# FPGAIO.net
KiCad netlist of a schematic drawn in Altium Designer
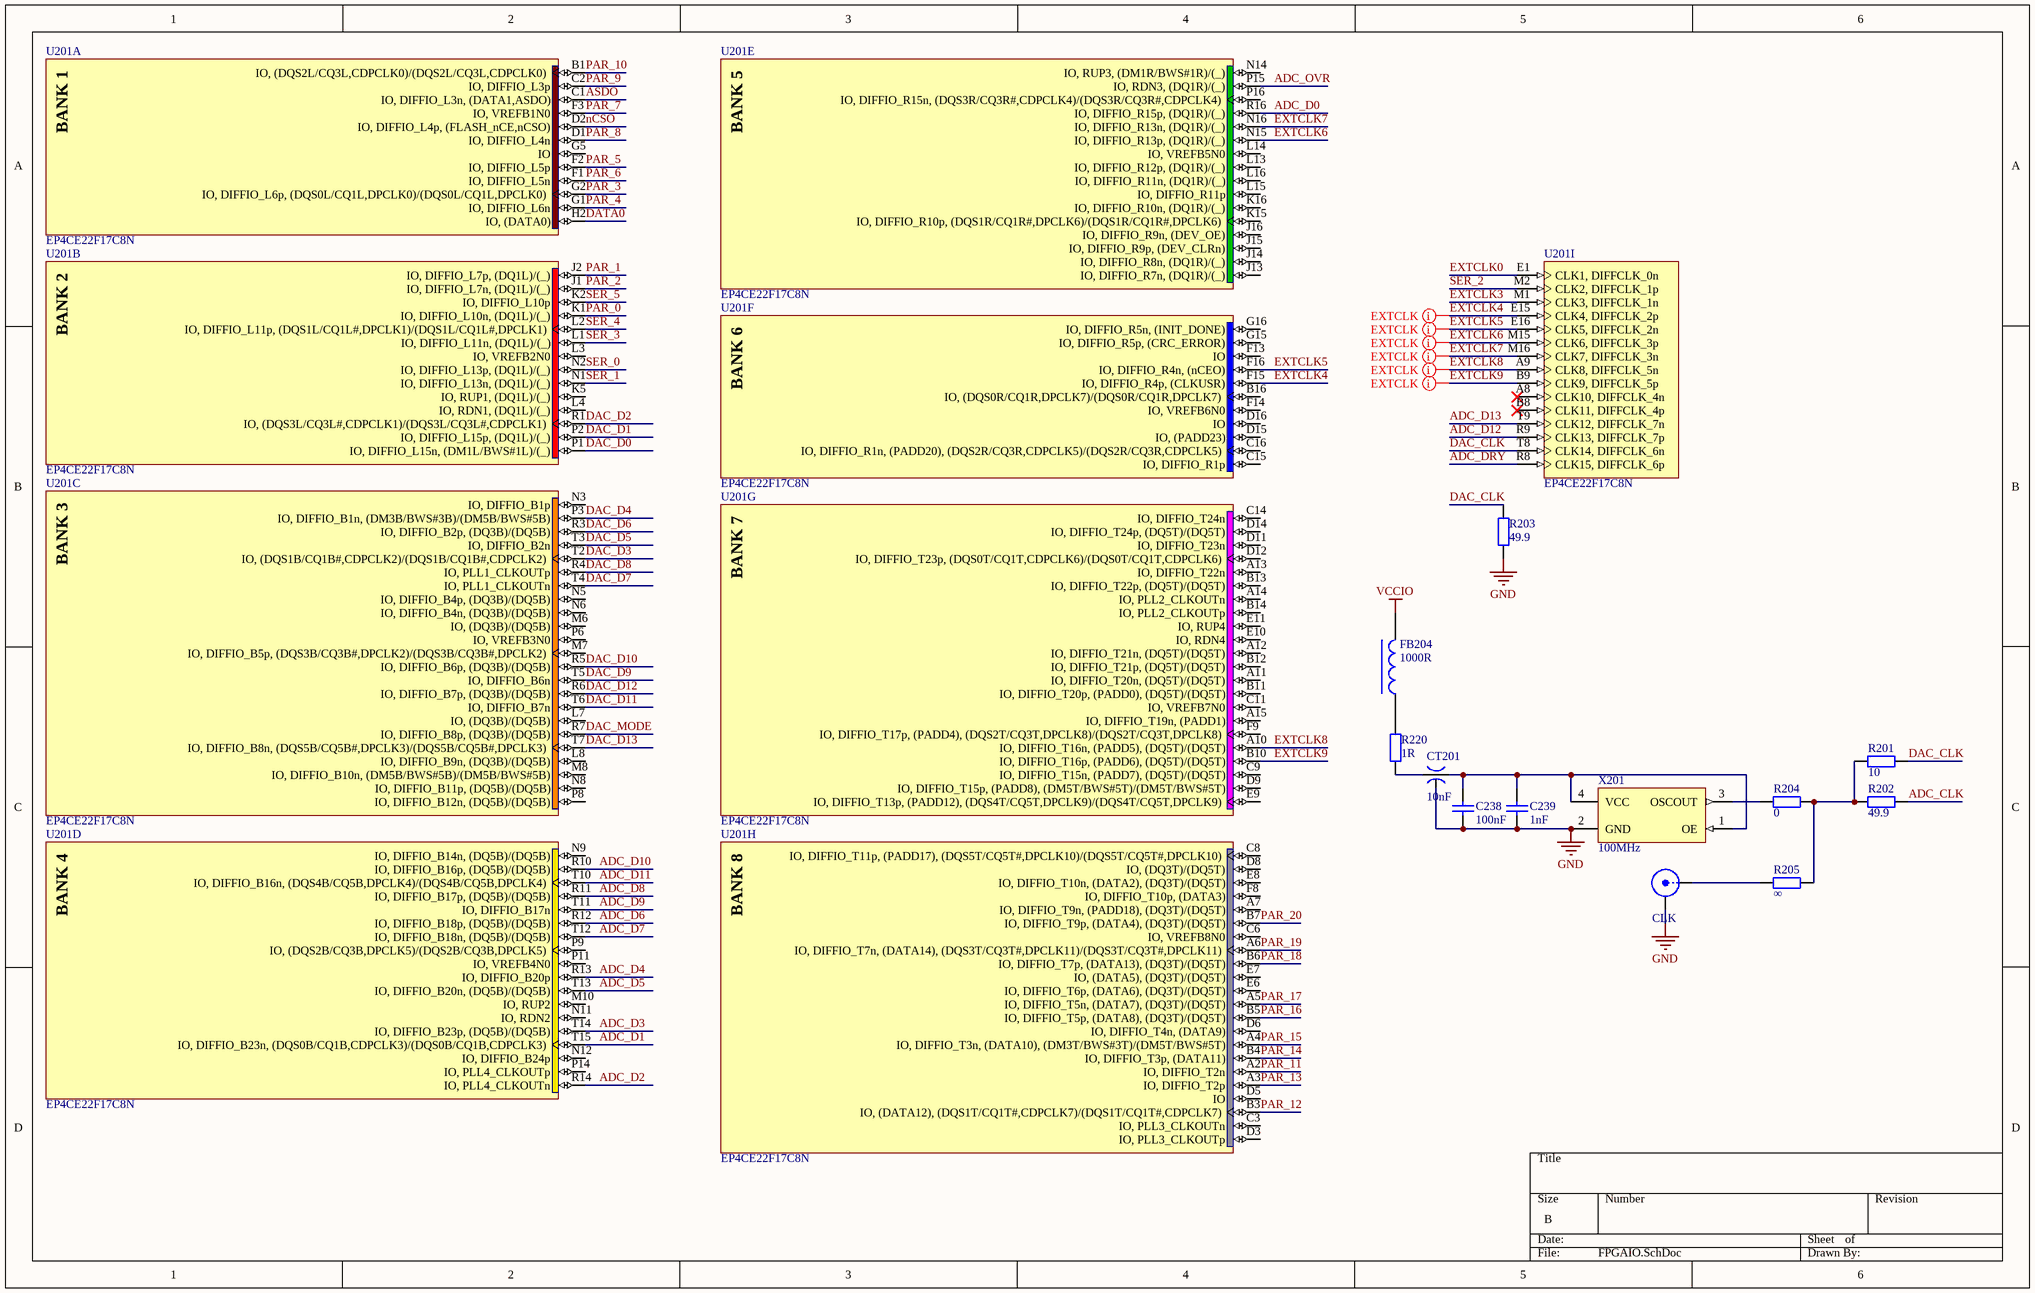
[diagram p0: FPGAIO.SchDoc]

(export (version "E")
  (design (tool "Eeschema 10.0.6"))
  (components
    (comp (ref "C238")
      (value "100nF")
      (footprint "0402C")
      (description "MLCC")
      (libsource (lib "Misc") (part "MLCC"))
    )
    (comp (ref "C239")
      (value "1nF")
      (footprint "0402C")
      (description "MLCC")
      (libsource (lib "Misc") (part "MLCC"))
    )
    (comp (ref "CLK")
      (value "SMA")
      (footprint "SMA-V-NARROW")
      (description "SMA Connector")
      (libsource (lib "SMA") (part "SMA"))
    )
    (comp (ref "CT201")
      (value "10nF")
      (footprint "CAPC0603TH")
      (description "3-terminal capacitor")
      (fields (field (name "Comment") "CAP-TH"))
      (libsource (lib "Misc") (part "CAP-TH"))
    )
    (comp (ref "FB204")
      (value "1000R")
      (footprint "0603L")
      (description "FerriteBead")
      (libsource (lib "Misc") (part "FerriteBead"))
    )
    (comp (ref "R201")
      (value "10")
      (footprint "0402R")
      (description "Resistor")
      (libsource (lib "") (part "Resistor_1"))
    )
    (comp (ref "R202")
      (value "49.9")
      (footprint "0402R")
      (description "Resistor")
      (libsource (lib "") (part "Resistor_1"))
    )
    (comp (ref "R203")
      (value "49.9")
      (footprint "0402R")
      (description "Resistor")
      (libsource (lib "Misc") (part "Resistor"))
    )
    (comp (ref "R204")
      (value "0")
      (footprint "0402R")
      (description "Resistor")
      (libsource (lib "") (part "Resistor_1"))
    )
    (comp (ref "R205")
      (value "∞")
      (footprint "0402R")
      (description "Resistor")
      (libsource (lib "") (part "Resistor_1"))
    )
    (comp (ref "R220")
      (value "1R")
      (footprint "0603R")
      (description "Resistor")
      (libsource (lib "Misc") (part "Resistor"))
    )
    (comp (ref "U201")
      (value "EP4CE22F17C8N")
      (footprint "FBGA256_A-155")
      (fields (field (name "MANUFACTURER") "Altera"))
      (libsource (lib "Altera Cyclone IV E") (part "EP4CE22F17C8N"))
    )
    (comp (ref "X201")
      (value "100MHz")
      (footprint "XTAL-7050")
      (description "Oscillator")
      (libsource (lib "XTAL") (part "Oscillator"))
    )
  )
  (nets
    (net (code "1") (name "/ADC_CLK") (class "Default")
      (node (ref "R202") (pin "2") (pinfunction "2_2") (pintype "passive"))
    )
    (net (code "2") (name "/ADC_D0") (class "Default")
      (node (ref "U201") (pin "R16") (pinfunction "IO,_DIFFIO_R15p,_(DQ1R)/(_)_R16") (pintype "bidirectional"))
    )
    (net (code "3") (name "/ADC_D1") (class "Default")
      (node (ref "U201") (pin "T15") (pinfunction "IO,_DIFFIO_B23n,_(DQS0B/CQ1B,CDPCLK3)/(DQS0B/CQ1B,CDPCLK3)_T15") (pintype "bidirectional"))
    )
    (net (code "4") (name "/ADC_D2") (class "Default")
      (node (ref "U201") (pin "R14") (pinfunction "IO,_PLL4_CLKOUTn_R14") (pintype "bidirectional"))
    )
    (net (code "5") (name "/ADC_D3") (class "Default")
      (node (ref "U201") (pin "T14") (pinfunction "IO,_DIFFIO_B23p,_(DQ5B)/(DQ5B)_T14") (pintype "bidirectional"))
    )
    (net (code "6") (name "/ADC_D4") (class "Default")
      (node (ref "U201") (pin "R13") (pinfunction "IO,_DIFFIO_B20p_R13") (pintype "bidirectional"))
    )
    (net (code "7") (name "/ADC_D5") (class "Default")
      (node (ref "U201") (pin "T13") (pinfunction "IO,_DIFFIO_B20n,_(DQ5B)/(DQ5B)_T13") (pintype "bidirectional"))
    )
    (net (code "8") (name "/ADC_D6") (class "Default")
      (node (ref "U201") (pin "R12") (pinfunction "IO,_DIFFIO_B18p,_(DQ5B)/(DQ5B)_R12") (pintype "bidirectional"))
    )
    (net (code "9") (name "/ADC_D7") (class "Default")
      (node (ref "U201") (pin "T12") (pinfunction "IO,_DIFFIO_B18n,_(DQ5B)/(DQ5B)_T12") (pintype "bidirectional"))
    )
    (net (code "10") (name "/ADC_D8") (class "Default")
      (node (ref "U201") (pin "R11") (pinfunction "IO,_DIFFIO_B17p,_(DQ5B)/(DQ5B)_R11") (pintype "bidirectional"))
    )
    (net (code "11") (name "/ADC_D9") (class "Default")
      (node (ref "U201") (pin "T11") (pinfunction "IO,_DIFFIO_B17n_T11") (pintype "bidirectional"))
    )
    (net (code "12") (name "/ADC_D10") (class "Default")
      (node (ref "U201") (pin "R10") (pinfunction "IO,_DIFFIO_B16p,_(DQ5B)/(DQ5B)_R10") (pintype "bidirectional"))
    )
    (net (code "13") (name "/ADC_D11") (class "Default")
      (node (ref "U201") (pin "T10") (pinfunction "IO,_DIFFIO_B16n,_(DQS4B/CQ5B,DPCLK4)/(DQS4B/CQ5B,DPCLK4)_T10") (pintype "bidirectional"))
    )
    (net (code "14") (name "/ADC_D12") (class "Default")
      (node (ref "U201") (pin "R9") (pinfunction "CLK13,_DIFFCLK_7p_R9") (pintype "input"))
    )
    (net (code "15") (name "/ADC_D13") (class "Default")
      (node (ref "U201") (pin "T9") (pinfunction "CLK12,_DIFFCLK_7n_T9") (pintype "input"))
    )
    (net (code "16") (name "/ADC_DRY") (class "Default")
      (node (ref "U201") (pin "R8") (pinfunction "CLK15,_DIFFCLK_6p_R8") (pintype "input"))
    )
    (net (code "17") (name "/ADC_OVR") (class "Default")
      (node (ref "U201") (pin "P15") (pinfunction "IO,_RDN3,_(DQ1R)/(_)_P15") (pintype "bidirectional"))
    )
    (net (code "18") (name "/ASDO") (class "Default")
      (node (ref "U201") (pin "C1") (pinfunction "IO,_DIFFIO_L3n,_(DATA1,ASDO)_C1") (pintype "bidirectional"))
    )
    (net (code "19") (name "/DAC_CLK") (class "Default")
      (node (ref "R201") (pin "2") (pinfunction "2_2") (pintype "passive"))
      (node (ref "R203") (pin "2") (pinfunction "2_2") (pintype "passive"))
      (node (ref "U201") (pin "T8") (pinfunction "CLK14,_DIFFCLK_6n_T8") (pintype "input"))
    )
    (net (code "20") (name "/DAC_D0") (class "Default")
      (node (ref "U201") (pin "P1") (pinfunction "IO,_DIFFIO_L15n,_(DM1L/BWS#1L)/(_)_P1") (pintype "bidirectional"))
    )
    (net (code "21") (name "/DAC_D1") (class "Default")
      (node (ref "U201") (pin "P2") (pinfunction "IO,_DIFFIO_L15p,_(DQ1L)/(_)_P2") (pintype "bidirectional"))
    )
    (net (code "22") (name "/DAC_D2") (class "Default")
      (node (ref "U201") (pin "R1") (pinfunction "IO,_(DQS3L/CQ3L#,CDPCLK1)/(DQS3L/CQ3L#,CDPCLK1)_R1") (pintype "bidirectional"))
    )
    (net (code "23") (name "/DAC_D3") (class "Default")
      (node (ref "U201") (pin "T2") (pinfunction "IO,_(DQS1B/CQ1B#,CDPCLK2)/(DQS1B/CQ1B#,CDPCLK2)_T2") (pintype "bidirectional"))
    )
    (net (code "24") (name "/DAC_D4") (class "Default")
      (node (ref "U201") (pin "P3") (pinfunction "IO,_DIFFIO_B1n,_(DM3B/BWS#3B)/(DM5B/BWS#5B)_P3") (pintype "bidirectional"))
    )
    (net (code "25") (name "/DAC_D5") (class "Default")
      (node (ref "U201") (pin "T3") (pinfunction "IO,_DIFFIO_B2n_T3") (pintype "bidirectional"))
    )
    (net (code "26") (name "/DAC_D6") (class "Default")
      (node (ref "U201") (pin "R3") (pinfunction "IO,_DIFFIO_B2p,_(DQ3B)/(DQ5B)_R3") (pintype "bidirectional"))
    )
    (net (code "27") (name "/DAC_D7") (class "Default")
      (node (ref "U201") (pin "T4") (pinfunction "IO,_PLL1_CLKOUTn_T4") (pintype "bidirectional"))
    )
    (net (code "28") (name "/DAC_D8") (class "Default")
      (node (ref "U201") (pin "R4") (pinfunction "IO,_PLL1_CLKOUTp_R4") (pintype "bidirectional"))
    )
    (net (code "29") (name "/DAC_D9") (class "Default")
      (node (ref "U201") (pin "T5") (pinfunction "IO,_DIFFIO_B6n_T5") (pintype "bidirectional"))
    )
    (net (code "30") (name "/DAC_D10") (class "Default")
      (node (ref "U201") (pin "R5") (pinfunction "IO,_DIFFIO_B6p,_(DQ3B)/(DQ5B)_R5") (pintype "bidirectional"))
    )
    (net (code "31") (name "/DAC_D11") (class "Default")
      (node (ref "U201") (pin "T6") (pinfunction "IO,_DIFFIO_B7n_T6") (pintype "bidirectional"))
    )
    (net (code "32") (name "/DAC_D12") (class "Default")
      (node (ref "U201") (pin "R6") (pinfunction "IO,_DIFFIO_B7p,_(DQ3B)/(DQ5B)_R6") (pintype "bidirectional"))
    )
    (net (code "33") (name "/DAC_D13") (class "Default")
      (node (ref "U201") (pin "T7") (pinfunction "IO,_DIFFIO_B8n,_(DQS5B/CQ5B#,DPCLK3)/(DQS5B/CQ5B#,DPCLK3)_T7") (pintype "bidirectional"))
    )
    (net (code "34") (name "/DAC_MODE") (class "Default")
      (node (ref "U201") (pin "R7") (pinfunction "IO,_DIFFIO_B8p,_(DQ3B)/(DQ5B)_R7") (pintype "bidirectional"))
    )
    (net (code "35") (name "/DATA0") (class "Default")
      (node (ref "U201") (pin "H2") (pinfunction "IO,_(DATA0)_H2") (pintype "bidirectional"))
    )
    (net (code "36") (name "/EXTCLK0") (class "Default")
      (node (ref "U201") (pin "E1") (pinfunction "CLK1,_DIFFCLK_0n_E1") (pintype "input"))
    )
    (net (code "37") (name "/EXTCLK3") (class "Default")
      (node (ref "U201") (pin "M1") (pinfunction "CLK3,_DIFFCLK_1n_M1") (pintype "input"))
    )
    (net (code "38") (name "/EXTCLK4") (class "Default")
      (node (ref "U201") (pin "E15") (pinfunction "CLK4,_DIFFCLK_2p_E15") (pintype "input"))
      (node (ref "U201") (pin "F15") (pinfunction "IO,_DIFFIO_R4p,_(CLKUSR)_F15") (pintype "bidirectional"))
    )
    (net (code "39") (name "/EXTCLK5") (class "Default")
      (node (ref "U201") (pin "E16") (pinfunction "CLK5,_DIFFCLK_2n_E16") (pintype "input"))
      (node (ref "U201") (pin "F16") (pinfunction "IO,_DIFFIO_R4n,_(nCEO)_F16") (pintype "bidirectional"))
    )
    (net (code "40") (name "/EXTCLK6") (class "Default")
      (node (ref "U201") (pin "M15") (pinfunction "CLK6,_DIFFCLK_3p_M15") (pintype "input"))
      (node (ref "U201") (pin "N15") (pinfunction "IO,_DIFFIO_R13p,_(DQ1R)/(_)_N15") (pintype "bidirectional"))
    )
    (net (code "41") (name "/EXTCLK7") (class "Default")
      (node (ref "U201") (pin "M16") (pinfunction "CLK7,_DIFFCLK_3n_M16") (pintype "input"))
      (node (ref "U201") (pin "N16") (pinfunction "IO,_DIFFIO_R13n,_(DQ1R)/(_)_N16") (pintype "bidirectional"))
    )
    (net (code "42") (name "/EXTCLK8") (class "Default")
      (node (ref "U201") (pin "A10") (pinfunction "IO,_DIFFIO_T16n,_(PADD5),_(DQ5T)/(DQ5T)_A10") (pintype "bidirectional"))
      (node (ref "U201") (pin "A9") (pinfunction "CLK8,_DIFFCLK_5n_A9") (pintype "input"))
    )
    (net (code "43") (name "/EXTCLK9") (class "Default")
      (node (ref "U201") (pin "B10") (pinfunction "IO,_DIFFIO_T16p,_(PADD6),_(DQ5T)/(DQ5T)_B10") (pintype "bidirectional"))
      (node (ref "U201") (pin "B9") (pinfunction "CLK9,_DIFFCLK_5p_B9") (pintype "input"))
    )
    (net (code "44") (name "/PAR_0") (class "Default")
      (node (ref "U201") (pin "K1") (pinfunction "IO,_DIFFIO_L10n,_(DQ1L)/(_)_K1") (pintype "bidirectional"))
    )
    (net (code "45") (name "/PAR_1") (class "Default")
      (node (ref "U201") (pin "J2") (pinfunction "IO,_DIFFIO_L7p,_(DQ1L)/(_)_J2") (pintype "bidirectional"))
    )
    (net (code "46") (name "/PAR_2") (class "Default")
      (node (ref "U201") (pin "J1") (pinfunction "IO,_DIFFIO_L7n,_(DQ1L)/(_)_J1") (pintype "bidirectional"))
    )
    (net (code "47") (name "/PAR_3") (class "Default")
      (node (ref "U201") (pin "G2") (pinfunction "IO,_DIFFIO_L6p,_(DQS0L/CQ1L,DPCLK0)/(DQS0L/CQ1L,DPCLK0)_G2") (pintype "bidirectional"))
    )
    (net (code "48") (name "/PAR_4") (class "Default")
      (node (ref "U201") (pin "G1") (pinfunction "IO,_DIFFIO_L6n_G1") (pintype "bidirectional"))
    )
    (net (code "49") (name "/PAR_5") (class "Default")
      (node (ref "U201") (pin "F2") (pinfunction "IO,_DIFFIO_L5p_F2") (pintype "bidirectional"))
    )
    (net (code "50") (name "/PAR_6") (class "Default")
      (node (ref "U201") (pin "F1") (pinfunction "IO,_DIFFIO_L5n_F1") (pintype "bidirectional"))
    )
    (net (code "51") (name "/PAR_7") (class "Default")
      (node (ref "U201") (pin "F3") (pinfunction "IO,_VREFB1N0_F3") (pintype "bidirectional"))
    )
    (net (code "52") (name "/PAR_8") (class "Default")
      (node (ref "U201") (pin "D1") (pinfunction "IO,_DIFFIO_L4n_D1") (pintype "bidirectional"))
    )
    (net (code "53") (name "/PAR_9") (class "Default")
      (node (ref "U201") (pin "C2") (pinfunction "IO,_DIFFIO_L3p_C2") (pintype "bidirectional"))
    )
    (net (code "54") (name "/PAR_10") (class "Default")
      (node (ref "U201") (pin "B1") (pinfunction "IO,_(DQS2L/CQ3L,CDPCLK0)/(DQS2L/CQ3L,CDPCLK0)_B1") (pintype "bidirectional"))
    )
    (net (code "55") (name "/PAR_11") (class "Default")
      (node (ref "U201") (pin "A2") (pinfunction "IO,_DIFFIO_T2n_A2") (pintype "bidirectional"))
    )
    (net (code "56") (name "/PAR_12") (class "Default")
      (node (ref "U201") (pin "B3") (pinfunction "IO,_(DATA12),_(DQS1T/CQ1T#,CDPCLK7)/(DQS1T/CQ1T#,CDPCLK7)_B3") (pintype "bidirectional"))
    )
    (net (code "57") (name "/PAR_13") (class "Default")
      (node (ref "U201") (pin "A3") (pinfunction "IO,_DIFFIO_T2p_A3") (pintype "bidirectional"))
    )
    (net (code "58") (name "/PAR_14") (class "Default")
      (node (ref "U201") (pin "B4") (pinfunction "IO,_DIFFIO_T3p,_(DATA11)_B4") (pintype "bidirectional"))
    )
    (net (code "59") (name "/PAR_15") (class "Default")
      (node (ref "U201") (pin "A4") (pinfunction "IO,_DIFFIO_T3n,_(DATA10),_(DM3T/BWS#3T)/(DM5T/BWS#5T)_A4") (pintype "bidirectional"))
    )
    (net (code "60") (name "/PAR_16") (class "Default")
      (node (ref "U201") (pin "B5") (pinfunction "IO,_DIFFIO_T5p,_(DATA8),_(DQ3T)/(DQ5T)_B5") (pintype "bidirectional"))
    )
    (net (code "61") (name "/PAR_17") (class "Default")
      (node (ref "U201") (pin "A5") (pinfunction "IO,_DIFFIO_T5n,_(DATA7),_(DQ3T)/(DQ5T)_A5") (pintype "bidirectional"))
    )
    (net (code "62") (name "/PAR_18") (class "Default")
      (node (ref "U201") (pin "B6") (pinfunction "IO,_DIFFIO_T7p,_(DATA13),_(DQ3T)/(DQ5T)_B6") (pintype "bidirectional"))
    )
    (net (code "63") (name "/PAR_19") (class "Default")
      (node (ref "U201") (pin "A6") (pinfunction "IO,_DIFFIO_T7n,_(DATA14),_(DQS3T/CQ3T#,DPCLK11)/(DQS3T/CQ3T#,DPCLK11)_A6") (pintype "bidirectional"))
    )
    (net (code "64") (name "/PAR_20") (class "Default")
      (node (ref "U201") (pin "B7") (pinfunction "IO,_DIFFIO_T9p,_(DATA4),_(DQ3T)/(DQ5T)_B7") (pintype "bidirectional"))
    )
    (net (code "65") (name "/SER_0") (class "Default")
      (node (ref "U201") (pin "N2") (pinfunction "IO,_DIFFIO_L13p,_(DQ1L)/(_)_N2") (pintype "bidirectional"))
    )
    (net (code "66") (name "/SER_1") (class "Default")
      (node (ref "U201") (pin "N1") (pinfunction "IO,_DIFFIO_L13n,_(DQ1L)/(_)_N1") (pintype "bidirectional"))
    )
    (net (code "67") (name "/SER_2") (class "Default")
      (node (ref "U201") (pin "M2") (pinfunction "CLK2,_DIFFCLK_1p_M2") (pintype "input"))
    )
    (net (code "68") (name "/SER_3") (class "Default")
      (node (ref "U201") (pin "L1") (pinfunction "IO,_DIFFIO_L11n,_(DQ1L)/(_)_L1") (pintype "bidirectional"))
    )
    (net (code "69") (name "/SER_4") (class "Default")
      (node (ref "U201") (pin "L2") (pinfunction "IO,_DIFFIO_L11p,_(DQS1L/CQ1L#,DPCLK1)/(DQS1L/CQ1L#,DPCLK1)_L2") (pintype "bidirectional"))
    )
    (net (code "70") (name "/SER_5") (class "Default")
      (node (ref "U201") (pin "K2") (pinfunction "IO,_DIFFIO_L10p_K2") (pintype "bidirectional"))
    )
    (net (code "71") (name "/nCSO") (class "Default")
      (node (ref "U201") (pin "D2") (pinfunction "IO,_DIFFIO_L4p,_(FLASH_nCE,nCSO)_D2") (pintype "bidirectional"))
    )
    (net (code "72") (name "GND") (class "Default")
      (node (ref "C238") (pin "1") (pinfunction "1_1") (pintype "passive"))
      (node (ref "C239") (pin "1") (pinfunction "1_1") (pintype "passive"))
      (node (ref "CLK") (pin "2") (pinfunction "Y_2") (pintype "passive"))
      (node (ref "CT201") (pin "3") (pinfunction "3_3") (pintype "power_in"))
      (node (ref "R203") (pin "1") (pinfunction "1_1") (pintype "passive"))
      (node (ref "X201") (pin "2") (pinfunction "GND_2") (pintype "power_in"))
    )
    (net (code "73") (name "Net-(CLK-X)") (class "Default")
      (node (ref "CLK") (pin "1") (pinfunction "X_1") (pintype "passive"))
      (node (ref "R205") (pin "1") (pinfunction "1_1") (pintype "passive"))
    )
    (net (code "74") (name "Net-(CT201-Pad1)") (class "Default")
      (node (ref "CT201") (pin "1") (pinfunction "1_1") (pintype "power_in"))
      (node (ref "R220") (pin "1") (pinfunction "1_1") (pintype "passive"))
    )
    (net (code "75") (name "Net-(FB204-Pad1)") (class "Default")
      (node (ref "FB204") (pin "1") (pinfunction "1_1") (pintype "passive"))
      (node (ref "R220") (pin "2") (pinfunction "2_2") (pintype "passive"))
    )
    (net (code "76") (name "Net-(R201-Pad1)") (class "Default")
      (node (ref "R201") (pin "1") (pinfunction "1_1") (pintype "passive"))
      (node (ref "R202") (pin "1") (pinfunction "1_1") (pintype "passive"))
      (node (ref "R204") (pin "2") (pinfunction "2_2") (pintype "passive"))
      (node (ref "R205") (pin "2") (pinfunction "2_2") (pintype "passive"))
    )
    (net (code "77") (name "Net-(X201-OE)") (class "Default")
      (node (ref "C238") (pin "2") (pinfunction "2_2") (pintype "passive"))
      (node (ref "C239") (pin "2") (pinfunction "2_2") (pintype "passive"))
      (node (ref "CT201") (pin "2") (pinfunction "2_2") (pintype "power_in"))
      (node (ref "X201") (pin "1") (pinfunction "OE_1") (pintype "input"))
      (node (ref "X201") (pin "4") (pinfunction "VCC_4") (pintype "power_in"))
    )
    (net (code "78") (name "Net-(X201-OSCOUT)") (class "Default")
      (node (ref "R204") (pin "1") (pinfunction "1_1") (pintype "passive"))
      (node (ref "X201") (pin "3") (pinfunction "OSCOUT_3") (pintype "output"))
    )
    (net (code "79") (name "VCCIO") (class "Default")
      (node (ref "FB204") (pin "2") (pinfunction "2_2") (pintype "passive"))
    )
    (net (code "80") (name "unconnected-(U201A-IO-PadG5)") (class "Default")
      (node (ref "U201") (pin "G5") (pinfunction "IO_G5") (pintype "bidirectional"))
    )
    (net (code "81") (name "unconnected-(U201B-IO,_RDN1,_(DQ1L){slash}(_)-PadL4)") (class "Default")
      (node (ref "U201") (pin "L4") (pinfunction "IO,_RDN1,_(DQ1L)/(_)_L4") (pintype "bidirectional"))
    )
    (net (code "82") (name "unconnected-(U201B-IO,_RUP1,_(DQ1L){slash}(_)-PadK5)") (class "Default")
      (node (ref "U201") (pin "K5") (pinfunction "IO,_RUP1,_(DQ1L)/(_)_K5") (pintype "bidirectional"))
    )
    (net (code "83") (name "unconnected-(U201B-IO,_VREFB2N0-PadL3)") (class "Default")
      (node (ref "U201") (pin "L3") (pinfunction "IO,_VREFB2N0_L3") (pintype "bidirectional"))
    )
    (net (code "84") (name "unconnected-(U201C-IO,_(DQ3B){slash}(DQ5B)-PadL7)") (class "Default")
      (node (ref "U201") (pin "L7") (pinfunction "IO,_(DQ3B)/(DQ5B)_L7") (pintype "bidirectional"))
    )
    (net (code "85") (name "unconnected-(U201C-IO,_(DQ3B){slash}(DQ5B)-PadM6)") (class "Default")
      (node (ref "U201") (pin "M6") (pinfunction "IO,_(DQ3B)/(DQ5B)_M6") (pintype "bidirectional"))
    )
    (net (code "86") (name "unconnected-(U201C-IO,_DIFFIO_B1p-PadN3)") (class "Default")
      (node (ref "U201") (pin "N3") (pinfunction "IO,_DIFFIO_B1p_N3") (pintype "bidirectional"))
    )
    (net (code "87") (name "unconnected-(U201C-IO,_DIFFIO_B4n,_(DQ3B){slash}(DQ5B)-PadN6)") (class "Default")
      (node (ref "U201") (pin "N6") (pinfunction "IO,_DIFFIO_B4n,_(DQ3B)/(DQ5B)_N6") (pintype "bidirectional"))
    )
    (net (code "88") (name "unconnected-(U201C-IO,_DIFFIO_B4p,_(DQ3B){slash}(DQ5B)-PadN5)") (class "Default")
      (node (ref "U201") (pin "N5") (pinfunction "IO,_DIFFIO_B4p,_(DQ3B)/(DQ5B)_N5") (pintype "bidirectional"))
    )
    (net (code "89") (name "unconnected-(U201C-IO,_DIFFIO_B5p,_(DQS3B{slash}CQ3B#,DPCLK2){slash}(DQS3B{slash}CQ3B#,DPCLK2)-PadM7)") (class "Default")
      (node (ref "U201") (pin "M7") (pinfunction "IO,_DIFFIO_B5p,_(DQS3B/CQ3B#,DPCLK2)/(DQS3B/CQ3B#,DPCLK2)_M7") (pintype "bidirectional"))
    )
    (net (code "90") (name "unconnected-(U201C-IO,_DIFFIO_B9n,_(DQ3B){slash}(DQ5B)-PadL8)") (class "Default")
      (node (ref "U201") (pin "L8") (pinfunction "IO,_DIFFIO_B9n,_(DQ3B)/(DQ5B)_L8") (pintype "bidirectional"))
    )
    (net (code "91") (name "unconnected-(U201C-IO,_DIFFIO_B10n,_(DM5B{slash}BWS#5B){slash}(DM5B{slash}BWS#5B)-PadM8)") (class "Default")
      (node (ref "U201") (pin "M8") (pinfunction "IO,_DIFFIO_B10n,_(DM5B/BWS#5B)/(DM5B/BWS#5B)_M8") (pintype "bidirectional"))
    )
    (net (code "92") (name "unconnected-(U201C-IO,_DIFFIO_B11p,_(DQ5B){slash}(DQ5B)-PadN8)") (class "Default")
      (node (ref "U201") (pin "N8") (pinfunction "IO,_DIFFIO_B11p,_(DQ5B)/(DQ5B)_N8") (pintype "bidirectional"))
    )
    (net (code "93") (name "unconnected-(U201C-IO,_DIFFIO_B12n,_(DQ5B){slash}(DQ5B)-PadP8)") (class "Default")
      (node (ref "U201") (pin "P8") (pinfunction "IO,_DIFFIO_B12n,_(DQ5B)/(DQ5B)_P8") (pintype "bidirectional"))
    )
    (net (code "94") (name "unconnected-(U201C-IO,_VREFB3N0-PadP6)") (class "Default")
      (node (ref "U201") (pin "P6") (pinfunction "IO,_VREFB3N0_P6") (pintype "bidirectional"))
    )
    (net (code "95") (name "unconnected-(U201D-IO,_(DQS2B{slash}CQ3B,DPCLK5){slash}(DQS2B{slash}CQ3B,DPCLK5)-PadP9)") (class "Default")
      (node (ref "U201") (pin "P9") (pinfunction "IO,_(DQS2B/CQ3B,DPCLK5)/(DQS2B/CQ3B,DPCLK5)_P9") (pintype "bidirectional"))
    )
    (net (code "96") (name "unconnected-(U201D-IO,_DIFFIO_B14n,_(DQ5B){slash}(DQ5B)-PadN9)") (class "Default")
      (node (ref "U201") (pin "N9") (pinfunction "IO,_DIFFIO_B14n,_(DQ5B)/(DQ5B)_N9") (pintype "bidirectional"))
    )
    (net (code "97") (name "unconnected-(U201D-IO,_DIFFIO_B24p-PadN12)") (class "Default")
      (node (ref "U201") (pin "N12") (pinfunction "IO,_DIFFIO_B24p_N12") (pintype "bidirectional"))
    )
    (net (code "98") (name "unconnected-(U201D-IO,_PLL4_CLKOUTp-PadP14)") (class "Default")
      (node (ref "U201") (pin "P14") (pinfunction "IO,_PLL4_CLKOUTp_P14") (pintype "bidirectional"))
    )
    (net (code "99") (name "unconnected-(U201D-IO,_RDN2-PadN11)") (class "Default")
      (node (ref "U201") (pin "N11") (pinfunction "IO,_RDN2_N11") (pintype "bidirectional"))
    )
    (net (code "100") (name "unconnected-(U201D-IO,_RUP2-PadM10)") (class "Default")
      (node (ref "U201") (pin "M10") (pinfunction "IO,_RUP2_M10") (pintype "bidirectional"))
    )
    (net (code "101") (name "unconnected-(U201D-IO,_VREFB4N0-PadP11)") (class "Default")
      (node (ref "U201") (pin "P11") (pinfunction "IO,_VREFB4N0_P11") (pintype "bidirectional"))
    )
    (net (code "102") (name "unconnected-(U201E-IO,_DIFFIO_R7n,_(DQ1R){slash}(_)-PadJ13)") (class "Default")
      (node (ref "U201") (pin "J13") (pinfunction "IO,_DIFFIO_R7n,_(DQ1R)/(_)_J13") (pintype "bidirectional"))
    )
    (net (code "103") (name "unconnected-(U201E-IO,_DIFFIO_R8n,_(DQ1R){slash}(_)-PadJ14)") (class "Default")
      (node (ref "U201") (pin "J14") (pinfunction "IO,_DIFFIO_R8n,_(DQ1R)/(_)_J14") (pintype "bidirectional"))
    )
    (net (code "104") (name "unconnected-(U201E-IO,_DIFFIO_R9n,_(DEV_OE)-PadJ16)") (class "Default")
      (node (ref "U201") (pin "J16") (pinfunction "IO,_DIFFIO_R9n,_(DEV_OE)_J16") (pintype "bidirectional"))
    )
    (net (code "105") (name "unconnected-(U201E-IO,_DIFFIO_R9p,_(DEV_CLRn)-PadJ15)") (class "Default")
      (node (ref "U201") (pin "J15") (pinfunction "IO,_DIFFIO_R9p,_(DEV_CLRn)_J15") (pintype "bidirectional"))
    )
    (net (code "106") (name "unconnected-(U201E-IO,_DIFFIO_R10n,_(DQ1R){slash}(_)-PadK16)") (class "Default")
      (node (ref "U201") (pin "K16") (pinfunction "IO,_DIFFIO_R10n,_(DQ1R)/(_)_K16") (pintype "bidirectional"))
    )
    (net (code "107") (name "unconnected-(U201E-IO,_DIFFIO_R10p,_(DQS1R{slash}CQ1R#,DPCLK6){slash}(DQS1R{slash}CQ1R#,DPCLK6)-PadK15)") (class "Default")
      (node (ref "U201") (pin "K15") (pinfunction "IO,_DIFFIO_R10p,_(DQS1R/CQ1R#,DPCLK6)/(DQS1R/CQ1R#,DPCLK6)_K15") (pintype "bidirectional"))
    )
    (net (code "108") (name "unconnected-(U201E-IO,_DIFFIO_R11n,_(DQ1R){slash}(_)-PadL16)") (class "Default")
      (node (ref "U201") (pin "L16") (pinfunction "IO,_DIFFIO_R11n,_(DQ1R)/(_)_L16") (pintype "bidirectional"))
    )
    (net (code "109") (name "unconnected-(U201E-IO,_DIFFIO_R11p-PadL15)") (class "Default")
      (node (ref "U201") (pin "L15") (pinfunction "IO,_DIFFIO_R11p_L15") (pintype "bidirectional"))
    )
    (net (code "110") (name "unconnected-(U201E-IO,_DIFFIO_R12p,_(DQ1R){slash}(_)-PadL13)") (class "Default")
      (node (ref "U201") (pin "L13") (pinfunction "IO,_DIFFIO_R12p,_(DQ1R)/(_)_L13") (pintype "bidirectional"))
    )
    (net (code "111") (name "unconnected-(U201E-IO,_DIFFIO_R15n,_(DQS3R{slash}CQ3R#,CDPCLK4){slash}(DQS3R{slash}CQ3R#,CDPCLK4)-PadP16)") (class "Default")
      (node (ref "U201") (pin "P16") (pinfunction "IO,_DIFFIO_R15n,_(DQS3R/CQ3R#,CDPCLK4)/(DQS3R/CQ3R#,CDPCLK4)_P16") (pintype "bidirectional"))
    )
    (net (code "112") (name "unconnected-(U201E-IO,_RUP3,_(DM1R{slash}BWS#1R){slash}(_)-PadN14)") (class "Default")
      (node (ref "U201") (pin "N14") (pinfunction "IO,_RUP3,_(DM1R/BWS#1R)/(_)_N14") (pintype "bidirectional"))
    )
    (net (code "113") (name "unconnected-(U201E-IO,_VREFB5N0-PadL14)") (class "Default")
      (node (ref "U201") (pin "L14") (pinfunction "IO,_VREFB5N0_L14") (pintype "bidirectional"))
    )
    (net (code "114") (name "unconnected-(U201F-IO,_(DQS0R{slash}CQ1R,DPCLK7){slash}(DQS0R{slash}CQ1R,DPCLK7)-PadB16)") (class "Default")
      (node (ref "U201") (pin "B16") (pinfunction "IO,_(DQS0R/CQ1R,DPCLK7)/(DQS0R/CQ1R,DPCLK7)_B16") (pintype "bidirectional"))
    )
    (net (code "115") (name "unconnected-(U201F-IO,_(PADD23)-PadD15)") (class "Default")
      (node (ref "U201") (pin "D15") (pinfunction "IO,_(PADD23)_D15") (pintype "bidirectional"))
    )
    (net (code "116") (name "unconnected-(U201F-IO,_DIFFIO_R1n,_(PADD20),_(DQS2R{slash}CQ3R,CDPCLK5){slash}(DQS2R{slash}CQ3R,CDPCLK5)-PadC16)") (class "Default")
      (node (ref "U201") (pin "C16") (pinfunction "IO,_DIFFIO_R1n,_(PADD20),_(DQS2R/CQ3R,CDPCLK5)/(DQS2R/CQ3R,CDPCLK5)_C16") (pintype "bidirectional"))
    )
    (net (code "117") (name "unconnected-(U201F-IO,_DIFFIO_R1p-PadC15)") (class "Default")
      (node (ref "U201") (pin "C15") (pinfunction "IO,_DIFFIO_R1p_C15") (pintype "bidirectional"))
    )
    (net (code "118") (name "unconnected-(U201F-IO,_DIFFIO_R5n,_(INIT_DONE)-PadG16)") (class "Default")
      (node (ref "U201") (pin "G16") (pinfunction "IO,_DIFFIO_R5n,_(INIT_DONE)_G16") (pintype "bidirectional"))
    )
    (net (code "119") (name "unconnected-(U201F-IO,_DIFFIO_R5p,_(CRC_ERROR)-PadG15)") (class "Default")
      (node (ref "U201") (pin "G15") (pinfunction "IO,_DIFFIO_R5p,_(CRC_ERROR)_G15") (pintype "bidirectional"))
    )
    (net (code "120") (name "unconnected-(U201F-IO,_VREFB6N0-PadF14)") (class "Default")
      (node (ref "U201") (pin "F14") (pinfunction "IO,_VREFB6N0_F14") (pintype "bidirectional"))
    )
    (net (code "121") (name "unconnected-(U201F-IO-PadD16)") (class "Default")
      (node (ref "U201") (pin "D16") (pinfunction "IO_D16") (pintype "bidirectional"))
    )
    (net (code "122") (name "unconnected-(U201F-IO-PadF13)") (class "Default")
      (node (ref "U201") (pin "F13") (pinfunction "IO_F13") (pintype "bidirectional"))
    )
    (net (code "123") (name "unconnected-(U201G-IO,_DIFFIO_T13p,_(PADD12),_(DQS4T{slash}CQ5T,DPCLK9){slash}(DQS4T{slash}CQ5T,DPCLK9)-PadE9)") (class "Default")
      (node (ref "U201") (pin "E9") (pinfunction "IO,_DIFFIO_T13p,_(PADD12),_(DQS4T/CQ5T,DPCLK9)/(DQS4T/CQ5T,DPCLK9)_E9") (pintype "bidirectional"))
    )
    (net (code "124") (name "unconnected-(U201G-IO,_DIFFIO_T15n,_(PADD7),_(DQ5T){slash}(DQ5T)-PadC9)") (class "Default")
      (node (ref "U201") (pin "C9") (pinfunction "IO,_DIFFIO_T15n,_(PADD7),_(DQ5T)/(DQ5T)_C9") (pintype "bidirectional"))
    )
    (net (code "125") (name "unconnected-(U201G-IO,_DIFFIO_T15p,_(PADD8),_(DM5T{slash}BWS#5T){slash}(DM5T{slash}BWS#5T)-PadD9)") (class "Default")
      (node (ref "U201") (pin "D9") (pinfunction "IO,_DIFFIO_T15p,_(PADD8),_(DM5T/BWS#5T)/(DM5T/BWS#5T)_D9") (pintype "bidirectional"))
    )
    (net (code "126") (name "unconnected-(U201G-IO,_DIFFIO_T17p,_(PADD4),_(DQS2T{slash}CQ3T,DPCLK8){slash}(DQS2T{slash}CQ3T,DPCLK8)-PadF9)") (class "Default")
      (node (ref "U201") (pin "F9") (pinfunction "IO,_DIFFIO_T17p,_(PADD4),_(DQS2T/CQ3T,DPCLK8)/(DQS2T/CQ3T,DPCLK8)_F9") (pintype "bidirectional"))
    )
    (net (code "127") (name "unconnected-(U201G-IO,_DIFFIO_T19n,_(PADD1)-PadA15)") (class "Default")
      (node (ref "U201") (pin "A15") (pinfunction "IO,_DIFFIO_T19n,_(PADD1)_A15") (pintype "bidirectional"))
    )
    (net (code "128") (name "unconnected-(U201G-IO,_DIFFIO_T20n,_(DQ5T){slash}(DQ5T)-PadA11)") (class "Default")
      (node (ref "U201") (pin "A11") (pinfunction "IO,_DIFFIO_T20n,_(DQ5T)/(DQ5T)_A11") (pintype "bidirectional"))
    )
    (net (code "129") (name "unconnected-(U201G-IO,_DIFFIO_T20p,_(PADD0),_(DQ5T){slash}(DQ5T)-PadB11)") (class "Default")
      (node (ref "U201") (pin "B11") (pinfunction "IO,_DIFFIO_T20p,_(PADD0),_(DQ5T)/(DQ5T)_B11") (pintype "bidirectional"))
    )
    (net (code "130") (name "unconnected-(U201G-IO,_DIFFIO_T21n,_(DQ5T){slash}(DQ5T)-PadA12)") (class "Default")
      (node (ref "U201") (pin "A12") (pinfunction "IO,_DIFFIO_T21n,_(DQ5T)/(DQ5T)_A12") (pintype "bidirectional"))
    )
    (net (code "131") (name "unconnected-(U201G-IO,_DIFFIO_T21p,_(DQ5T){slash}(DQ5T)-PadB12)") (class "Default")
      (node (ref "U201") (pin "B12") (pinfunction "IO,_DIFFIO_T21p,_(DQ5T)/(DQ5T)_B12") (pintype "bidirectional"))
    )
    (net (code "132") (name "unconnected-(U201G-IO,_DIFFIO_T22n-PadA13)") (class "Default")
      (node (ref "U201") (pin "A13") (pinfunction "IO,_DIFFIO_T22n_A13") (pintype "bidirectional"))
    )
    (net (code "133") (name "unconnected-(U201G-IO,_DIFFIO_T22p,_(DQ5T){slash}(DQ5T)-PadB13)") (class "Default")
      (node (ref "U201") (pin "B13") (pinfunction "IO,_DIFFIO_T22p,_(DQ5T)/(DQ5T)_B13") (pintype "bidirectional"))
    )
    (net (code "134") (name "unconnected-(U201G-IO,_DIFFIO_T23n-PadD11)") (class "Default")
      (node (ref "U201") (pin "D11") (pinfunction "IO,_DIFFIO_T23n_D11") (pintype "bidirectional"))
    )
    (net (code "135") (name "unconnected-(U201G-IO,_DIFFIO_T23p,_(DQS0T{slash}CQ1T,CDPCLK6){slash}(DQS0T{slash}CQ1T,CDPCLK6)-PadD12)") (class "Default")
      (node (ref "U201") (pin "D12") (pinfunction "IO,_DIFFIO_T23p,_(DQS0T/CQ1T,CDPCLK6)/(DQS0T/CQ1T,CDPCLK6)_D12") (pintype "bidirectional"))
    )
    (net (code "136") (name "unconnected-(U201G-IO,_DIFFIO_T24n-PadC14)") (class "Default")
      (node (ref "U201") (pin "C14") (pinfunction "IO,_DIFFIO_T24n_C14") (pintype "bidirectional"))
    )
    (net (code "137") (name "unconnected-(U201G-IO,_DIFFIO_T24p,_(DQ5T){slash}(DQ5T)-PadD14)") (class "Default")
      (node (ref "U201") (pin "D14") (pinfunction "IO,_DIFFIO_T24p,_(DQ5T)/(DQ5T)_D14") (pintype "bidirectional"))
    )
    (net (code "138") (name "unconnected-(U201G-IO,_PLL2_CLKOUTn-PadA14)") (class "Default")
      (node (ref "U201") (pin "A14") (pinfunction "IO,_PLL2_CLKOUTn_A14") (pintype "bidirectional"))
    )
    (net (code "139") (name "unconnected-(U201G-IO,_PLL2_CLKOUTp-PadB14)") (class "Default")
      (node (ref "U201") (pin "B14") (pinfunction "IO,_PLL2_CLKOUTp_B14") (pintype "bidirectional"))
    )
    (net (code "140") (name "unconnected-(U201G-IO,_RDN4-PadE10)") (class "Default")
      (node (ref "U201") (pin "E10") (pinfunction "IO,_RDN4_E10") (pintype "bidirectional"))
    )
    (net (code "141") (name "unconnected-(U201G-IO,_RUP4-PadE11)") (class "Default")
      (node (ref "U201") (pin "E11") (pinfunction "IO,_RUP4_E11") (pintype "bidirectional"))
    )
    (net (code "142") (name "unconnected-(U201G-IO,_VREFB7N0-PadC11)") (class "Default")
      (node (ref "U201") (pin "C11") (pinfunction "IO,_VREFB7N0_C11") (pintype "bidirectional"))
    )
    (net (code "143") (name "unconnected-(U201H-IO,_(DATA5),_(DQ3T){slash}(DQ5T)-PadE7)") (class "Default")
      (node (ref "U201") (pin "E7") (pinfunction "IO,_(DATA5),_(DQ3T)/(DQ5T)_E7") (pintype "bidirectional"))
    )
    (net (code "144") (name "unconnected-(U201H-IO,_(DQ3T){slash}(DQ5T)-PadD8)") (class "Default")
      (node (ref "U201") (pin "D8") (pinfunction "IO,_(DQ3T)/(DQ5T)_D8") (pintype "bidirectional"))
    )
    (net (code "145") (name "unconnected-(U201H-IO,_DIFFIO_T4n,_(DATA9)-PadD6)") (class "Default")
      (node (ref "U201") (pin "D6") (pinfunction "IO,_DIFFIO_T4n,_(DATA9)_D6") (pintype "bidirectional"))
    )
    (net (code "146") (name "unconnected-(U201H-IO,_DIFFIO_T6p,_(DATA6),_(DQ3T){slash}(DQ5T)-PadE6)") (class "Default")
      (node (ref "U201") (pin "E6") (pinfunction "IO,_DIFFIO_T6p,_(DATA6),_(DQ3T)/(DQ5T)_E6") (pintype "bidirectional"))
    )
    (net (code "147") (name "unconnected-(U201H-IO,_DIFFIO_T9n,_(PADD18),_(DQ3T){slash}(DQ5T)-PadA7)") (class "Default")
      (node (ref "U201") (pin "A7") (pinfunction "IO,_DIFFIO_T9n,_(PADD18),_(DQ3T)/(DQ5T)_A7") (pintype "bidirectional"))
    )
    (net (code "148") (name "unconnected-(U201H-IO,_DIFFIO_T10n,_(DATA2),_(DQ3T){slash}(DQ5T)-PadE8)") (class "Default")
      (node (ref "U201") (pin "E8") (pinfunction "IO,_DIFFIO_T10n,_(DATA2),_(DQ3T)/(DQ5T)_E8") (pintype "bidirectional"))
    )
    (net (code "149") (name "unconnected-(U201H-IO,_DIFFIO_T10p,_(DATA3)-PadF8)") (class "Default")
      (node (ref "U201") (pin "F8") (pinfunction "IO,_DIFFIO_T10p,_(DATA3)_F8") (pintype "bidirectional"))
    )
    (net (code "150") (name "unconnected-(U201H-IO,_DIFFIO_T11p,_(PADD17),_(DQS5T{slash}CQ5T#,DPCLK10){slash}(DQS5T{slash}CQ5T#,DPCLK10)-PadC8)") (class "Default")
      (node (ref "U201") (pin "C8") (pinfunction "IO,_DIFFIO_T11p,_(PADD17),_(DQS5T/CQ5T#,DPCLK10)/(DQS5T/CQ5T#,DPCLK10)_C8") (pintype "bidirectional"))
    )
    (net (code "151") (name "unconnected-(U201H-IO,_PLL3_CLKOUTn-PadC3)") (class "Default")
      (node (ref "U201") (pin "C3") (pinfunction "IO,_PLL3_CLKOUTn_C3") (pintype "bidirectional"))
    )
    (net (code "152") (name "unconnected-(U201H-IO,_PLL3_CLKOUTp-PadD3)") (class "Default")
      (node (ref "U201") (pin "D3") (pinfunction "IO,_PLL3_CLKOUTp_D3") (pintype "bidirectional"))
    )
    (net (code "153") (name "unconnected-(U201H-IO,_VREFB8N0-PadC6)") (class "Default")
      (node (ref "U201") (pin "C6") (pinfunction "IO,_VREFB8N0_C6") (pintype "bidirectional"))
    )
    (net (code "154") (name "unconnected-(U201H-IO-PadD5)") (class "Default")
      (node (ref "U201") (pin "D5") (pinfunction "IO_D5") (pintype "bidirectional"))
    )
    (net (code "155") (name "unconnected-(U201I-CLK10,_DIFFCLK_4n-PadA8)") (class "Default")
      (node (ref "U201") (pin "A8") (pinfunction "CLK10,_DIFFCLK_4n_A8") (pintype "input+no_connect"))
    )
    (net (code "156") (name "unconnected-(U201I-CLK11,_DIFFCLK_4p-PadB8)") (class "Default")
      (node (ref "U201") (pin "B8") (pinfunction "CLK11,_DIFFCLK_4p_B8") (pintype "input+no_connect"))
    )
  )
)
